# Schematic.net
KiCad netlist of a schematic drawn in Altium Designer
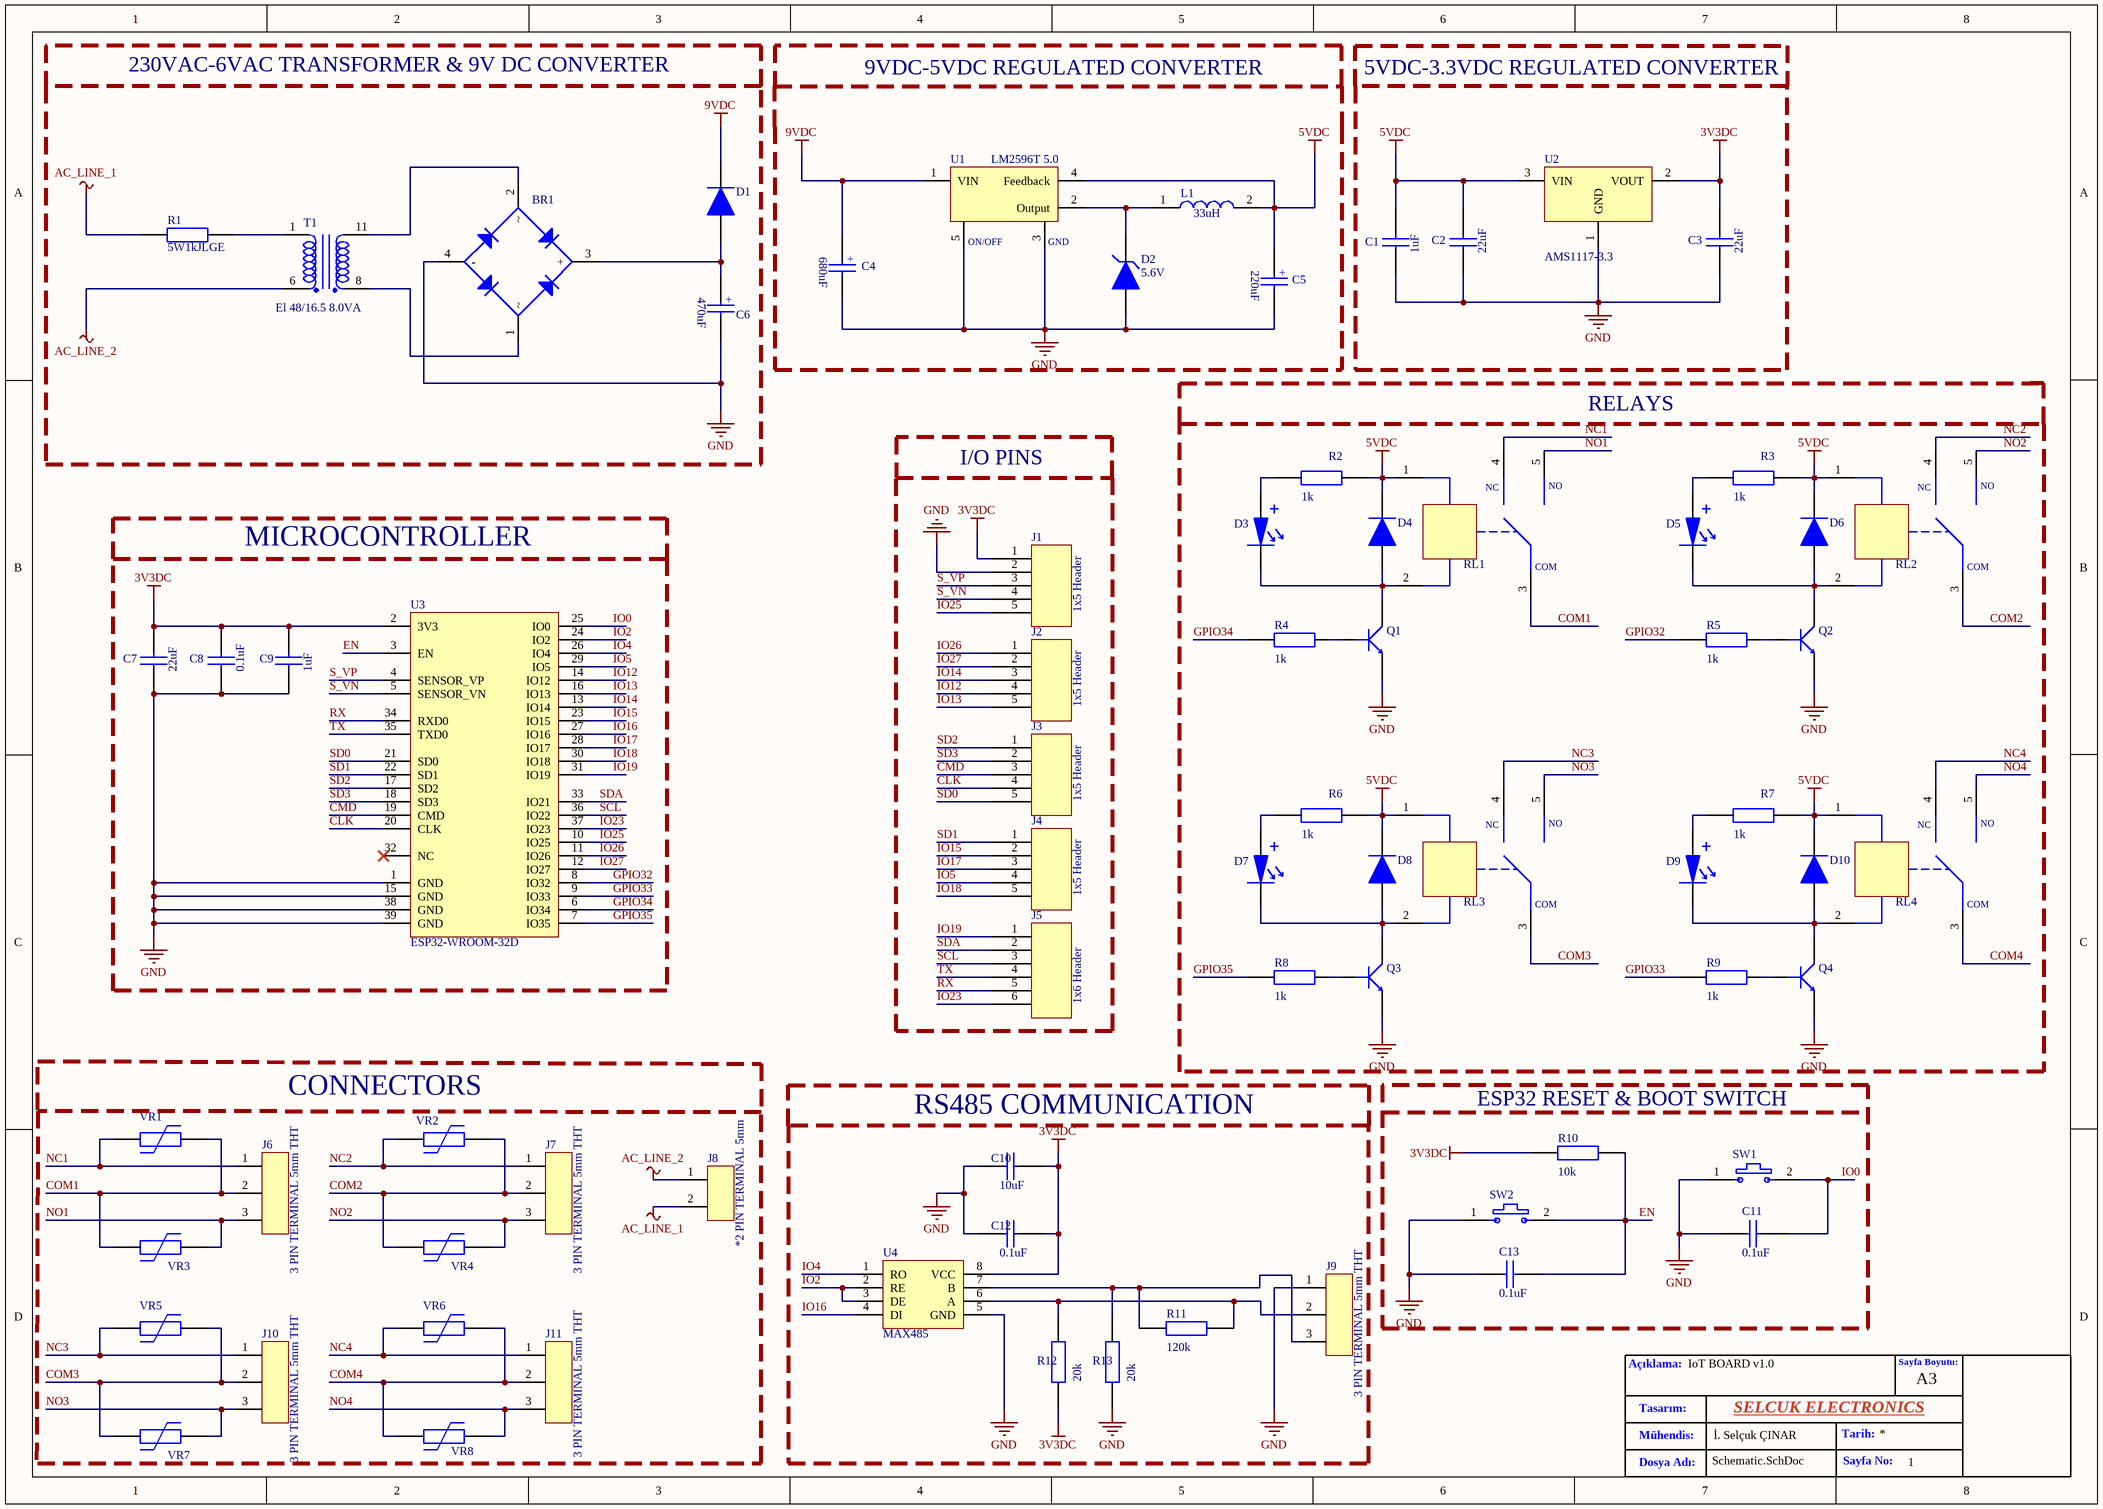
[diagram p0: Schematic.SchDoc]

(export (version "E")
  (design (tool "Eeschema 10.0.6"))
  (components
    (comp (ref "BR1")
      (value "MB10M")
      (footprint "MB10M")
      (description "Bridge Diode AC-DC")
      (libsource (lib "Sch_Lib") (part "MB10M"))
    )
    (comp (ref "C1")
      (value "CAP CER 22uF 0805")
      (footprint "CAP CER 1uF 0805")
      (description "1uF 16V 10% x5R 805 SMD Capacitor")
      (libsource (lib "Sch_Lib") (part "CAP CER 1uF 0805"))
    )
    (comp (ref "C2")
      (value "CAP CER 22uF 0805")
      (footprint "CAP CER 22uF 0805")
      (description "22uF 16V 10% x5R 805 SMD Capacitor")
      (libsource (lib "Sch_Lib") (part "CAP CER 22uF 0805"))
    )
    (comp (ref "C3")
      (value "CAP CER 22uF 0805")
      (footprint "CAP CER 22uF 0805")
      (description "22uF 16V 10% x5R 805 SMD Capacitor")
      (libsource (lib "Sch_Lib") (part "CAP CER 22uF 0805"))
    )
    (comp (ref "C4")
      (value "CAP ALU 680uF SMD RADIAL")
      (footprint "CAP ALU 680uF SMD RADIAL")
      (description "CAP ALU 680uF SMD")
      (libsource (lib "Sch_Lib") (part "CAP ALU 680uF SMD RADIAL"))
    )
    (comp (ref "C5")
      (value "CAP ALU 220uF SMD RADIAL")
      (footprint "CAP ALU 220uF SMD RADIAL")
      (description "CAP ALU 220uF SMD")
      (libsource (lib "Sch_Lib") (part "CAP ALU 220uF SMD RADIAL"))
    )
    (comp (ref "C6")
      (value "NOBBY")
      (footprint "CAP ALU 470uF THT")
      (description "CAP ALU 470uF Normal")
      (libsource (lib "Sch_Lib") (part "CAP ALU 470uF THT"))
    )
    (comp (ref "C7")
      (value "CAP CER 22uF 0805")
      (footprint "CAP CER 22uF 0805")
      (description "22uF 16V 10% x5R 805 SMD Capacitor")
      (libsource (lib "Sch_Lib") (part "CAP CER 22uF 0805"))
    )
    (comp (ref "C8")
      (value "CAP CER 0.1uF 0805")
      (footprint "CAP CER 0.1uF 0805")
      (description "0.1uF 16V 10% x5R 805 SMD Capacitor")
      (libsource (lib "Sch_Lib") (part "CAP CER 0.1uF 0805"))
    )
    (comp (ref "C9")
      (value "CAP CER 22uF 0805")
      (footprint "CAP CER 1uF 0805")
      (description "1uF 16V 10% x5R 805 SMD Capacitor")
      (libsource (lib "Sch_Lib") (part "CAP CER 1uF 0805"))
    )
    (comp (ref "C10")
      (value "CAP CER 22uF 0805")
      (footprint "CAP CER 10uF 0805")
      (description "10uF 16V 10% x5R 805 SMD Capacitor")
      (libsource (lib "Sch_Lib") (part "CAP CER 10uF 0805"))
    )
    (comp (ref "C11")
      (value "CAP CER 0.1uF 0805")
      (footprint "CAP CER 0.1uF 0805")
      (description "0.1uF 16V 10% x5R 805 SMD Capacitor")
      (libsource (lib "Sch_Lib") (part "CAP CER 0.1uF 0805"))
    )
    (comp (ref "C12")
      (value "CAP CER 0.1uF 0805")
      (footprint "CAP CER 0.1uF 0805")
      (description "0.1uF 16V 10% x5R 805 SMD Capacitor")
      (libsource (lib "Sch_Lib") (part "CAP CER 0.1uF 0805"))
    )
    (comp (ref "C13")
      (value "CAP CER 0.1uF 0805")
      (footprint "CAP CER 0.1uF 0805")
      (description "0.1uF 16V 10% x5R 805 SMD Capacitor")
      (libsource (lib "Sch_Lib") (part "CAP CER 0.1uF 0805"))
    )
    (comp (ref "D1")
      (value "M7-KT 1N4007 SMD")
      (footprint "M7-KT 1N4007 SMD")
      (description "M7-KT - 1N4007 - SMD Diyot 1A 1000V")
      (libsource (lib "Sch_Lib") (part "M7-KT 1N4007 SMD"))
    )
    (comp (ref "D2")
      (value "1SMB5919BT3G")
      (footprint "SMB")
      (description "Diode Zener Single 5.6V 5% 3W 2-Pin SMB T/R")
      (fields
        (field (name "MANUFACTURER") "ON Semiconductor")
        (field (name "TOLERANCE") "5%")
        (field (name "WORKING VOLTAGE") "5.6V")
        (field (name "DESIGNED BY") "BERK")
      )
      (libsource (lib "UDEMY_Library") (part "1SMB5919BT3G"))
    )
    (comp (ref "D3")
      (value "LED RED THT")
      (footprint "LED RED THT")
      (description "Throught LED")
      (libsource (lib "Sch_Lib") (part "LED RED THT"))
    )
    (comp (ref "D4")
      (value "M7-KT 1N4007 SMD")
      (footprint "M7-KT 1N4007 SMD")
      (description "M7-KT - 1N4007 - SMD Diyot 1A 1000V")
      (libsource (lib "Sch_Lib") (part "M7-KT 1N4007 SMD"))
    )
    (comp (ref "D5")
      (value "LED RED THT")
      (footprint "LED RED THT")
      (description "Throught LED")
      (libsource (lib "Sch_Lib") (part "LED RED THT"))
    )
    (comp (ref "D6")
      (value "M7-KT 1N4007 SMD")
      (footprint "M7-KT 1N4007 SMD")
      (description "M7-KT - 1N4007 - SMD Diyot 1A 1000V")
      (libsource (lib "Sch_Lib") (part "M7-KT 1N4007 SMD"))
    )
    (comp (ref "D7")
      (value "LED RED THT")
      (footprint "LED RED THT")
      (description "Throught LED")
      (libsource (lib "Sch_Lib") (part "LED RED THT"))
    )
    (comp (ref "D8")
      (value "M7-KT 1N4007 SMD")
      (footprint "M7-KT 1N4007 SMD")
      (description "M7-KT - 1N4007 - SMD Diyot 1A 1000V")
      (libsource (lib "Sch_Lib") (part "M7-KT 1N4007 SMD"))
    )
    (comp (ref "D9")
      (value "LED RED THT")
      (footprint "LED RED THT")
      (description "Throught LED")
      (libsource (lib "Sch_Lib") (part "LED RED THT"))
    )
    (comp (ref "D10")
      (value "M7-KT 1N4007 SMD")
      (footprint "M7-KT 1N4007 SMD")
      (description "M7-KT - 1N4007 - SMD Diyot 1A 1000V")
      (libsource (lib "Sch_Lib") (part "M7-KT 1N4007 SMD"))
    )
    (comp (ref "J1")
      (value "1x5 Header")
      (footprint "1x5 Header")
      (libsource (lib "Sch_Lib") (part "1x5 Header"))
    )
    (comp (ref "J2")
      (value "1x5 Header")
      (footprint "1x5 Header")
      (libsource (lib "Sch_Lib") (part "1x5 Header"))
    )
    (comp (ref "J3")
      (value "1x5 Header")
      (footprint "1x5 Header")
      (libsource (lib "Sch_Lib") (part "1x5 Header"))
    )
    (comp (ref "J4")
      (value "1x5 Header")
      (footprint "1x5 Header")
      (libsource (lib "Sch_Lib") (part "1x5 Header"))
    )
    (comp (ref "J5")
      (value "1x6 Header")
      (footprint "1x6 Header")
      (libsource (lib "Sch_Lib") (part "1x6 Header"))
    )
    (comp (ref "J6")
      (value "3 PIN TERMINAL 5mm THT")
      (footprint "3 PIN TERMINAL 5mm THT")
      (description "3 Position Wire to Board Terminal Block Horizontal with Board 0.197\" (5.00mm) Through Hole")
      (libsource (lib "Sch_Lib") (part "3 PIN TERMINAL 5mm THT"))
    )
    (comp (ref "J7")
      (value "3 PIN TERMINAL 5mm THT")
      (footprint "3 PIN TERMINAL 5mm THT")
      (description "3 Position Wire to Board Terminal Block Horizontal with Board 0.197\" (5.00mm) Through Hole")
      (libsource (lib "Sch_Lib") (part "3 PIN TERMINAL 5mm THT"))
    )
    (comp (ref "J8")
      (value "*2 PIN TERMINAL 5mm")
      (footprint "2 PIN TERMINAL 5mm THT")
      (description "2 Position Wire to Board Terminal Block Horizontal with Board 0.197\" (5.00mm) Through Hole")
      (libsource (lib "Sch_Lib") (part "2 PIN TERMINAL 5mm THT"))
    )
    (comp (ref "J9")
      (value "3 PIN TERMINAL 5mm THT")
      (footprint "3 PIN TERMINAL 5mm THT")
      (description "3 Position Wire to Board Terminal Block Horizontal with Board 0.197\" (5.00mm) Through Hole")
      (libsource (lib "Sch_Lib") (part "3 PIN TERMINAL 5mm THT"))
    )
    (comp (ref "J10")
      (value "3 PIN TERMINAL 5mm THT")
      (footprint "3 PIN TERMINAL 5mm THT")
      (description "3 Position Wire to Board Terminal Block Horizontal with Board 0.197\" (5.00mm) Through Hole")
      (libsource (lib "Sch_Lib") (part "3 PIN TERMINAL 5mm THT"))
    )
    (comp (ref "J11")
      (value "3 PIN TERMINAL 5mm THT")
      (footprint "3 PIN TERMINAL 5mm THT")
      (description "3 Position Wire to Board Terminal Block Horizontal with Board 0.197\" (5.00mm) Through Hole")
      (libsource (lib "Sch_Lib") (part "3 PIN TERMINAL 5mm THT"))
    )
    (comp (ref "L1")
      (value "SRR1260-330M")
      (footprint "SRR1260-330M")
      (description "33 µH Shielded Drum Core, Wirewound Inductor 3 A 60mOhm Max Nonstandard")
      (libsource (lib "Sch_Lib") (part "SRR1260-330M"))
    )
    (comp (ref "Q1")
      (value "BC847 NPN SMD SOT-23")
      (footprint "BC847 NPN SMD SOT-23")
      (description "BC847 Transistör NPN SMD SOT-23100mA, 45V")
      (libsource (lib "Sch_Lib") (part "BC847 NPN SMD SOT-23"))
    )
    (comp (ref "Q2")
      (value "BC847 NPN SMD SOT-23")
      (footprint "BC847 NPN SMD SOT-23")
      (description "BC847 Transistör NPN SMD SOT-23100mA, 45V")
      (libsource (lib "Sch_Lib") (part "BC847 NPN SMD SOT-23"))
    )
    (comp (ref "Q3")
      (value "BC847 NPN SMD SOT-23")
      (footprint "BC847 NPN SMD SOT-23")
      (description "BC847 Transistör NPN SMD SOT-23100mA, 45V")
      (libsource (lib "Sch_Lib") (part "BC847 NPN SMD SOT-23"))
    )
    (comp (ref "Q4")
      (value "BC847 NPN SMD SOT-23")
      (footprint "BC847 NPN SMD SOT-23")
      (description "BC847 Transistör NPN SMD SOT-23100mA, 45V")
      (libsource (lib "Sch_Lib") (part "BC847 NPN SMD SOT-23"))
    )
    (comp (ref "R1")
      (value "5W1kJLGE")
      (footprint "5W1kJLGE")
      (description "Resistor 5 Watt Cermet Wirewound Flameproof 1KOhm 5% Axial Lead")
      (libsource (lib "Sch_Lib") (part "5W1kJLGE"))
    )
    (comp (ref "R2")
      (value "RES 1K OHM 805")
      (footprint "RES 1K OHM 805")
      (description "1K 805 1/8 SMD Direnç")
      (libsource (lib "Sch_Lib") (part "RES 1K OHM 805"))
    )
    (comp (ref "R3")
      (value "RES 1K OHM 805")
      (footprint "RES 1K OHM 805")
      (description "1K 805 1/8 SMD Direnç")
      (libsource (lib "Sch_Lib") (part "RES 1K OHM 805"))
    )
    (comp (ref "R4")
      (value "RES 1K OHM 805")
      (footprint "RES 1K OHM 805")
      (description "1K 805 1/8 SMD Direnç")
      (libsource (lib "Sch_Lib") (part "RES 1K OHM 805"))
    )
    (comp (ref "R5")
      (value "RES 1K OHM 805")
      (footprint "RES 1K OHM 805")
      (description "1K 805 1/8 SMD Direnç")
      (libsource (lib "Sch_Lib") (part "RES 1K OHM 805"))
    )
    (comp (ref "R6")
      (value "RES 1K OHM 805")
      (footprint "RES 1K OHM 805")
      (description "1K 805 1/8 SMD Direnç")
      (libsource (lib "Sch_Lib") (part "RES 1K OHM 805"))
    )
    (comp (ref "R7")
      (value "RES 1K OHM 805")
      (footprint "RES 1K OHM 805")
      (description "1K 805 1/8 SMD Direnç")
      (libsource (lib "Sch_Lib") (part "RES 1K OHM 805"))
    )
    (comp (ref "R8")
      (value "RES 1K OHM 805")
      (footprint "RES 1K OHM 805")
      (description "1K 805 1/8 SMD Direnç")
      (libsource (lib "Sch_Lib") (part "RES 1K OHM 805"))
    )
    (comp (ref "R9")
      (value "RES 1K OHM 805")
      (footprint "RES 1K OHM 805")
      (description "1K 805 1/8 SMD Direnç")
      (libsource (lib "Sch_Lib") (part "RES 1K OHM 805"))
    )
    (comp (ref "R10")
      (value "RES 10K OHM 805")
      (footprint "RES 10K OHM 805")
      (description "10K 805 1/8 SMD Direnç")
      (libsource (lib "Sch_Lib") (part "RES 10K OHM 805"))
    )
    (comp (ref "R11")
      (value "RES 120R OHM 805")
      (footprint "RES 120R OHM 805")
      (description "120Ohm 805 1/8 SMD Direnç")
      (libsource (lib "Sch_Lib") (part "RES 120R OHM 805"))
    )
    (comp (ref "R12")
      (value "RES 20K OHM 805")
      (footprint "RES 20K OHM 805")
      (description "20K 805 1/8 SMD Direnç")
      (libsource (lib "Sch_Lib") (part "RES 20K OHM 805"))
    )
    (comp (ref "R13")
      (value "RES 20K OHM 805")
      (footprint "RES 20K OHM 805")
      (description "20K 805 1/8 SMD Direnç")
      (libsource (lib "Sch_Lib") (part "RES 20K OHM 805"))
    )
    (comp (ref "RL1")
      (value "SRD-03VDC-SL-C")
      (footprint "SRD-03VDC-SL-C")
      (description "Relays General Purpose Non Latching 3VDC SPDT 10A (250VAC) Max 5PIN")
      (libsource (lib "Sch_Lib") (part "SRD-03VDC-SL-C"))
    )
    (comp (ref "RL2")
      (value "SRD-03VDC-SL-C")
      (footprint "SRD-03VDC-SL-C")
      (description "Relays General Purpose Non Latching 3VDC SPDT 10A (250VAC) Max 5PIN")
      (libsource (lib "Sch_Lib") (part "SRD-03VDC-SL-C"))
    )
    (comp (ref "RL3")
      (value "SRD-03VDC-SL-C")
      (footprint "SRD-03VDC-SL-C")
      (description "Relays General Purpose Non Latching 3VDC SPDT 10A (250VAC) Max 5PIN")
      (libsource (lib "Sch_Lib") (part "SRD-03VDC-SL-C"))
    )
    (comp (ref "RL4")
      (value "SRD-03VDC-SL-C")
      (footprint "SRD-03VDC-SL-C")
      (description "Relays General Purpose Non Latching 3VDC SPDT 10A (250VAC) Max 5PIN")
      (libsource (lib "Sch_Lib") (part "SRD-03VDC-SL-C"))
    )
    (comp (ref "SW1")
      (value "SKRKAEE010")
      (footprint "SKRKAEE010")
      (description "Switch Tactile N.O. SPST Round Button Gull Wing 0.05A 12VDC 1.57N SMD T/R")
      (libsource (lib "Sch_Lib") (part "SKRKAEE010"))
    )
    (comp (ref "SW2")
      (value "SKRKAEE010")
      (footprint "SKRKAEE010")
      (description "Switch Tactile N.O. SPST Round Button Gull Wing 0.05A 12VDC 1.57N SMD T/R")
      (libsource (lib "Sch_Lib") (part "SKRKAEE010"))
    )
    (comp (ref "T1")
      (value "El 48/16.5 8.0VA")
      (footprint "El 48/16.5 8.0VA")
      (description "230VAC-6VAC Transformer 8VA")
      (libsource (lib "Sch_Lib") (part "El 48/16.5 8.0VA"))
    )
    (comp (ref "U1")
      (value "LM2596T 5.0")
      (footprint "LM2596T 5.0")
      (description "SIMPLE SWITCHER&reg; 4.5V to 40V, 3A Low Component Count Step-Down Regulator 5-TO-220")
      (libsource (lib "Sch_Lib") (part "LM2596T 5.0"))
    )
    (comp (ref "U2")
      (value "AMS1117-3.3")
      (footprint "AMS1117-3.3")
      (description "Sot223/Pkg 1-Amp 3.3-Volt Low Drop Out Voltage Regulatator")
      (libsource (lib "Sch_Lib") (part "AMS1117-3.3"))
    )
    (comp (ref "U3")
      (value "ESP32-WROOM-32D")
      (footprint "ESP32-WROOM-32D")
      (description "SMD MODULE, ESP32-D0WDQ6, 32MBIT")
      (libsource (lib "Sch_Lib") (part "ESP32-WROOM-32D"))
    )
    (comp (ref "U4")
      (value "MAX485")
      (footprint "MAX485")
      (description "1/1 Transceiver Half RS422, RS485 8-uMAX-EP¦8-uSOP-EP")
      (libsource (lib "Sch_Lib") (part "MAX485"))
    )
    (comp (ref "VR1")
      (value "B72210S0151K101")
      (footprint "B72210S0151K101")
      (description "240 V 2.5 kA Varistor 1 Circuit Through Hole Disc 10mm")
      (libsource (lib "Sch_Lib") (part "B72210S0151K101"))
    )
    (comp (ref "VR2")
      (value "B72210S0151K101")
      (footprint "B72210S0151K101")
      (description "240 V 2.5 kA Varistor 1 Circuit Through Hole Disc 10mm")
      (libsource (lib "Sch_Lib") (part "B72210S0151K101"))
    )
    (comp (ref "VR3")
      (value "B72210S0151K101")
      (footprint "B72210S0151K101")
      (description "240 V 2.5 kA Varistor 1 Circuit Through Hole Disc 10mm")
      (libsource (lib "Sch_Lib") (part "B72210S0151K101"))
    )
    (comp (ref "VR4")
      (value "B72210S0151K101")
      (footprint "B72210S0151K101")
      (description "240 V 2.5 kA Varistor 1 Circuit Through Hole Disc 10mm")
      (libsource (lib "Sch_Lib") (part "B72210S0151K101"))
    )
    (comp (ref "VR5")
      (value "B72210S0151K101")
      (footprint "B72210S0151K101")
      (description "240 V 2.5 kA Varistor 1 Circuit Through Hole Disc 10mm")
      (libsource (lib "Sch_Lib") (part "B72210S0151K101"))
    )
    (comp (ref "VR6")
      (value "B72210S0151K101")
      (footprint "B72210S0151K101")
      (description "240 V 2.5 kA Varistor 1 Circuit Through Hole Disc 10mm")
      (libsource (lib "Sch_Lib") (part "B72210S0151K101"))
    )
    (comp (ref "VR7")
      (value "B72210S0151K101")
      (footprint "B72210S0151K101")
      (description "240 V 2.5 kA Varistor 1 Circuit Through Hole Disc 10mm")
      (libsource (lib "Sch_Lib") (part "B72210S0151K101"))
    )
    (comp (ref "VR8")
      (value "B72210S0151K101")
      (footprint "B72210S0151K101")
      (description "240 V 2.5 kA Varistor 1 Circuit Through Hole Disc 10mm")
      (libsource (lib "Sch_Lib") (part "B72210S0151K101"))
    )
  )
  (nets
    (net (code "1") (name "/CLK") (class "Default")
      (node (ref "J3") (pin "4") (pinfunction "4_4") (pintype "passive"))
      (node (ref "U3") (pin "20") (pinfunction "CLK_20") (pintype "passive"))
    )
    (net (code "2") (name "/CMD") (class "Default")
      (node (ref "J3") (pin "3") (pinfunction "3_3") (pintype "passive"))
      (node (ref "U3") (pin "19") (pinfunction "CMD_19") (pintype "passive"))
    )
    (net (code "3") (name "/COM1") (class "Default")
      (node (ref "J6") (pin "2") (pinfunction "2_2") (pintype "passive"))
      (node (ref "RL1") (pin "3") (pinfunction "COM_3") (pintype "passive"))
      (node (ref "VR1") (pin "2") (pinfunction "2_2") (pintype "passive"))
      (node (ref "VR3") (pin "1") (pinfunction "1_1") (pintype "passive"))
    )
    (net (code "4") (name "/COM2") (class "Default")
      (node (ref "J7") (pin "2") (pinfunction "2_2") (pintype "passive"))
      (node (ref "RL2") (pin "3") (pinfunction "COM_3") (pintype "passive"))
      (node (ref "VR2") (pin "2") (pinfunction "2_2") (pintype "passive"))
      (node (ref "VR4") (pin "1") (pinfunction "1_1") (pintype "passive"))
    )
    (net (code "5") (name "/COM3") (class "Default")
      (node (ref "J10") (pin "2") (pinfunction "2_2") (pintype "passive"))
      (node (ref "RL3") (pin "3") (pinfunction "COM_3") (pintype "passive"))
      (node (ref "VR5") (pin "2") (pinfunction "2_2") (pintype "passive"))
      (node (ref "VR7") (pin "1") (pinfunction "1_1") (pintype "passive"))
    )
    (net (code "6") (name "/COM4") (class "Default")
      (node (ref "J11") (pin "2") (pinfunction "2_2") (pintype "passive"))
      (node (ref "RL4") (pin "3") (pinfunction "COM_3") (pintype "passive"))
      (node (ref "VR6") (pin "2") (pinfunction "2_2") (pintype "passive"))
      (node (ref "VR8") (pin "1") (pinfunction "1_1") (pintype "passive"))
    )
    (net (code "7") (name "/EN") (class "Default")
      (node (ref "C13") (pin "2") (pinfunction "2_2") (pintype "passive"))
      (node (ref "R10") (pin "2") (pinfunction "2_2") (pintype "passive"))
      (node (ref "SW2") (pin "2") (pinfunction "2_2") (pintype "passive"))
      (node (ref "U3") (pin "3") (pinfunction "EN_3") (pintype "passive"))
    )
    (net (code "8") (name "/GPIO32") (class "Default")
      (node (ref "R5") (pin "1") (pinfunction "1_1") (pintype "passive"))
      (node (ref "U3") (pin "8") (pinfunction "IO32_8") (pintype "passive"))
    )
    (net (code "9") (name "/GPIO33") (class "Default")
      (node (ref "R9") (pin "1") (pinfunction "1_1") (pintype "passive"))
      (node (ref "U3") (pin "9") (pinfunction "IO33_9") (pintype "passive"))
    )
    (net (code "10") (name "/GPIO34") (class "Default")
      (node (ref "R4") (pin "1") (pinfunction "1_1") (pintype "passive"))
      (node (ref "U3") (pin "6") (pinfunction "IO34_6") (pintype "passive"))
    )
    (net (code "11") (name "/GPIO35") (class "Default")
      (node (ref "R8") (pin "1") (pinfunction "1_1") (pintype "passive"))
      (node (ref "U3") (pin "7") (pinfunction "IO35_7") (pintype "passive"))
    )
    (net (code "12") (name "/IO0") (class "Default")
      (node (ref "C11") (pin "2") (pinfunction "2_2") (pintype "passive"))
      (node (ref "SW1") (pin "2") (pinfunction "2_2") (pintype "passive"))
      (node (ref "U3") (pin "25") (pinfunction "IO0_25") (pintype "passive"))
    )
    (net (code "13") (name "/IO2") (class "Default")
      (node (ref "U3") (pin "24") (pinfunction "IO2_24") (pintype "passive"))
      (node (ref "U4") (pin "2") (pinfunction "RE_2") (pintype "passive"))
      (node (ref "U4") (pin "3") (pinfunction "DE_3") (pintype "passive"))
    )
    (net (code "14") (name "/IO4") (class "Default")
      (node (ref "U3") (pin "26") (pinfunction "IO4_26") (pintype "passive"))
      (node (ref "U4") (pin "1") (pinfunction "RO_1") (pintype "passive"))
    )
    (net (code "15") (name "/IO5") (class "Default")
      (node (ref "J4") (pin "4") (pinfunction "4_4") (pintype "passive"))
      (node (ref "U3") (pin "29") (pinfunction "IO5_29") (pintype "passive"))
    )
    (net (code "16") (name "/IO12") (class "Default")
      (node (ref "J2") (pin "4") (pinfunction "4_4") (pintype "passive"))
      (node (ref "U3") (pin "14") (pinfunction "IO12_14") (pintype "passive"))
    )
    (net (code "17") (name "/IO13") (class "Default")
      (node (ref "J2") (pin "5") (pinfunction "5_5") (pintype "passive"))
      (node (ref "U3") (pin "16") (pinfunction "IO13_16") (pintype "passive"))
    )
    (net (code "18") (name "/IO14") (class "Default")
      (node (ref "J2") (pin "3") (pinfunction "3_3") (pintype "passive"))
      (node (ref "U3") (pin "13") (pinfunction "IO14_13") (pintype "passive"))
    )
    (net (code "19") (name "/IO15") (class "Default")
      (node (ref "J4") (pin "2") (pinfunction "2_2") (pintype "passive"))
      (node (ref "U3") (pin "23") (pinfunction "IO15_23") (pintype "passive"))
    )
    (net (code "20") (name "/IO16") (class "Default")
      (node (ref "U3") (pin "27") (pinfunction "IO16_27") (pintype "passive"))
      (node (ref "U4") (pin "4") (pinfunction "DI_4") (pintype "passive"))
    )
    (net (code "21") (name "/IO17") (class "Default")
      (node (ref "J4") (pin "3") (pinfunction "3_3") (pintype "passive"))
      (node (ref "U3") (pin "28") (pinfunction "IO17_28") (pintype "passive"))
    )
    (net (code "22") (name "/IO18") (class "Default")
      (node (ref "J4") (pin "5") (pinfunction "5_5") (pintype "passive"))
      (node (ref "U3") (pin "30") (pinfunction "IO18_30") (pintype "passive"))
    )
    (net (code "23") (name "/IO19") (class "Default")
      (node (ref "J5") (pin "1") (pinfunction "1_1") (pintype "passive"))
      (node (ref "U3") (pin "31") (pinfunction "IO19_31") (pintype "passive"))
    )
    (net (code "24") (name "/IO23") (class "Default")
      (node (ref "J5") (pin "6") (pinfunction "6_6") (pintype "passive"))
      (node (ref "U3") (pin "37") (pinfunction "IO23_37") (pintype "passive"))
    )
    (net (code "25") (name "/IO25") (class "Default")
      (node (ref "J1") (pin "5") (pinfunction "5_5") (pintype "passive"))
      (node (ref "U3") (pin "10") (pinfunction "IO25_10") (pintype "passive"))
    )
    (net (code "26") (name "/IO26") (class "Default")
      (node (ref "J2") (pin "1") (pinfunction "1_1") (pintype "passive"))
      (node (ref "U3") (pin "11") (pinfunction "IO26_11") (pintype "passive"))
    )
    (net (code "27") (name "/IO27") (class "Default")
      (node (ref "J2") (pin "2") (pinfunction "2_2") (pintype "passive"))
      (node (ref "U3") (pin "12") (pinfunction "IO27_12") (pintype "passive"))
    )
    (net (code "28") (name "/NC1") (class "Default")
      (node (ref "J6") (pin "1") (pinfunction "1_1") (pintype "passive"))
      (node (ref "RL1") (pin "4") (pinfunction "NC_4") (pintype "passive"))
      (node (ref "VR1") (pin "1") (pinfunction "1_1") (pintype "passive"))
    )
    (net (code "29") (name "/NC2") (class "Default")
      (node (ref "J7") (pin "1") (pinfunction "1_1") (pintype "passive"))
      (node (ref "RL2") (pin "4") (pinfunction "NC_4") (pintype "passive"))
      (node (ref "VR2") (pin "1") (pinfunction "1_1") (pintype "passive"))
    )
    (net (code "30") (name "/NC3") (class "Default")
      (node (ref "J10") (pin "1") (pinfunction "1_1") (pintype "passive"))
      (node (ref "RL3") (pin "4") (pinfunction "NC_4") (pintype "passive"))
      (node (ref "VR5") (pin "1") (pinfunction "1_1") (pintype "passive"))
    )
    (net (code "31") (name "/NC4") (class "Default")
      (node (ref "J11") (pin "1") (pinfunction "1_1") (pintype "passive"))
      (node (ref "RL4") (pin "4") (pinfunction "NC_4") (pintype "passive"))
      (node (ref "VR6") (pin "1") (pinfunction "1_1") (pintype "passive"))
    )
    (net (code "32") (name "/NO1") (class "Default")
      (node (ref "J6") (pin "3") (pinfunction "3_3") (pintype "passive"))
      (node (ref "RL1") (pin "5") (pinfunction "NO_5") (pintype "passive"))
      (node (ref "VR3") (pin "2") (pinfunction "2_2") (pintype "passive"))
    )
    (net (code "33") (name "/NO2") (class "Default")
      (node (ref "J7") (pin "3") (pinfunction "3_3") (pintype "passive"))
      (node (ref "RL2") (pin "5") (pinfunction "NO_5") (pintype "passive"))
      (node (ref "VR4") (pin "2") (pinfunction "2_2") (pintype "passive"))
    )
    (net (code "34") (name "/NO3") (class "Default")
      (node (ref "J10") (pin "3") (pinfunction "3_3") (pintype "passive"))
      (node (ref "RL3") (pin "5") (pinfunction "NO_5") (pintype "passive"))
      (node (ref "VR7") (pin "2") (pinfunction "2_2") (pintype "passive"))
    )
    (net (code "35") (name "/NO4") (class "Default")
      (node (ref "J11") (pin "3") (pinfunction "3_3") (pintype "passive"))
      (node (ref "RL4") (pin "5") (pinfunction "NO_5") (pintype "passive"))
      (node (ref "VR8") (pin "2") (pinfunction "2_2") (pintype "passive"))
    )
    (net (code "36") (name "/RX") (class "Default")
      (node (ref "J5") (pin "5") (pinfunction "5_5") (pintype "passive"))
      (node (ref "U3") (pin "34") (pinfunction "RXD0_34") (pintype "passive"))
    )
    (net (code "37") (name "/SCL") (class "Default")
      (node (ref "J5") (pin "3") (pinfunction "3_3") (pintype "passive"))
      (node (ref "U3") (pin "36") (pinfunction "IO22_36") (pintype "passive"))
    )
    (net (code "38") (name "/SD0") (class "Default")
      (node (ref "J3") (pin "5") (pinfunction "5_5") (pintype "passive"))
      (node (ref "U3") (pin "21") (pinfunction "SD0_21") (pintype "passive"))
    )
    (net (code "39") (name "/SD1") (class "Default")
      (node (ref "J4") (pin "1") (pinfunction "1_1") (pintype "passive"))
      (node (ref "U3") (pin "22") (pinfunction "SD1_22") (pintype "passive"))
    )
    (net (code "40") (name "/SD2") (class "Default")
      (node (ref "J3") (pin "1") (pinfunction "1_1") (pintype "passive"))
      (node (ref "U3") (pin "17") (pinfunction "SD2_17") (pintype "passive"))
    )
    (net (code "41") (name "/SD3") (class "Default")
      (node (ref "J3") (pin "2") (pinfunction "2_2") (pintype "passive"))
      (node (ref "U3") (pin "18") (pinfunction "SD3_18") (pintype "passive"))
    )
    (net (code "42") (name "/SDA") (class "Default")
      (node (ref "J5") (pin "2") (pinfunction "2_2") (pintype "passive"))
      (node (ref "U3") (pin "33") (pinfunction "IO21_33") (pintype "passive"))
    )
    (net (code "43") (name "/S_VN") (class "Default")
      (node (ref "J1") (pin "4") (pinfunction "4_4") (pintype "passive"))
      (node (ref "U3") (pin "5") (pinfunction "SENSOR_VN_5") (pintype "passive"))
    )
    (net (code "44") (name "/S_VP") (class "Default")
      (node (ref "J1") (pin "3") (pinfunction "3_3") (pintype "passive"))
      (node (ref "U3") (pin "4") (pinfunction "SENSOR_VP_4") (pintype "passive"))
    )
    (net (code "45") (name "/TX") (class "Default")
      (node (ref "J5") (pin "4") (pinfunction "4_4") (pintype "passive"))
      (node (ref "U3") (pin "35") (pinfunction "TXD0_35") (pintype "passive"))
    )
    (net (code "46") (name "3V3DC") (class "Default")
      (node (ref "C10") (pin "2") (pinfunction "2_2") (pintype "passive"))
      (node (ref "C12") (pin "2") (pinfunction "2_2") (pintype "passive"))
      (node (ref "C3") (pin "2") (pinfunction "2_2") (pintype "passive"))
      (node (ref "C7") (pin "2") (pinfunction "2_2") (pintype "passive"))
      (node (ref "C8") (pin "2") (pinfunction "2_2") (pintype "passive"))
      (node (ref "C9") (pin "2") (pinfunction "2_2") (pintype "passive"))
      (node (ref "J1") (pin "1") (pinfunction "1_1") (pintype "passive"))
      (node (ref "R10") (pin "1") (pinfunction "1_1") (pintype "passive"))
      (node (ref "R12") (pin "1") (pinfunction "1_1") (pintype "passive"))
      (node (ref "U2") (pin "2") (pinfunction "VOUT_2") (pintype "passive"))
      (node (ref "U3") (pin "2") (pinfunction "3V3_2") (pintype "passive"))
      (node (ref "U4") (pin "8") (pinfunction "VCC_8") (pintype "passive"))
    )
    (net (code "47") (name "5VDC") (class "Default")
      (node (ref "C1") (pin "2") (pinfunction "2_2") (pintype "passive"))
      (node (ref "C2") (pin "2") (pinfunction "2_2") (pintype "passive"))
      (node (ref "C5") (pin "1") (pinfunction "1_1") (pintype "passive"))
      (node (ref "D10") (pin "2") (pinfunction "2_2") (pintype "power_in"))
      (node (ref "D4") (pin "2") (pinfunction "2_2") (pintype "power_in"))
      (node (ref "D6") (pin "2") (pinfunction "2_2") (pintype "power_in"))
      (node (ref "D8") (pin "2") (pinfunction "2_2") (pintype "power_in"))
      (node (ref "L1") (pin "2") (pinfunction "2_2") (pintype "passive"))
      (node (ref "R2") (pin "2") (pinfunction "2_2") (pintype "passive"))
      (node (ref "R3") (pin "2") (pinfunction "2_2") (pintype "passive"))
      (node (ref "R6") (pin "2") (pinfunction "2_2") (pintype "passive"))
      (node (ref "R7") (pin "2") (pinfunction "2_2") (pintype "passive"))
      (node (ref "RL1") (pin "1") (pinfunction "+_1") (pintype "passive"))
      (node (ref "RL2") (pin "1") (pinfunction "+_1") (pintype "passive"))
      (node (ref "RL3") (pin "1") (pinfunction "+_1") (pintype "passive"))
      (node (ref "RL4") (pin "1") (pinfunction "+_1") (pintype "passive"))
      (node (ref "U1") (pin "4") (pinfunction "Feedback_4") (pintype "passive"))
      (node (ref "U2") (pin "3") (pinfunction "VIN_3") (pintype "passive"))
    )
    (net (code "48") (name "9VDC") (class "Default")
      (node (ref "C4") (pin "1") (pinfunction "1_1") (pintype "passive"))
      (node (ref "D1") (pin "2") (pinfunction "2_2") (pintype "power_in"))
      (node (ref "U1") (pin "1") (pinfunction "VIN_1") (pintype "passive"))
    )
    (net (code "49") (name "AC_LINE_1") (class "Default")
      (node (ref "J8") (pin "2") (pinfunction "2_2") (pintype "passive"))
      (node (ref "R1") (pin "1") (pinfunction "1_1") (pintype "passive"))
    )
    (net (code "50") (name "AC_LINE_2") (class "Default")
      (node (ref "J8") (pin "1") (pinfunction "1_1") (pintype "passive"))
      (node (ref "T1") (pin "6") (pinfunction "6_6") (pintype "passive"))
    )
    (net (code "51") (name "GND") (class "Default")
      (node (ref "BR1") (pin "4") (pinfunction "-_4") (pintype "passive"))
      (node (ref "C1") (pin "1") (pinfunction "1_1") (pintype "passive"))
      (node (ref "C10") (pin "1") (pinfunction "1_1") (pintype "passive"))
      (node (ref "C11") (pin "1") (pinfunction "1_1") (pintype "passive"))
      (node (ref "C12") (pin "1") (pinfunction "1_1") (pintype "passive"))
      (node (ref "C13") (pin "1") (pinfunction "1_1") (pintype "passive"))
      (node (ref "C2") (pin "1") (pinfunction "1_1") (pintype "passive"))
      (node (ref "C3") (pin "1") (pinfunction "1_1") (pintype "passive"))
      (node (ref "C4") (pin "2") (pinfunction "2_2") (pintype "passive"))
      (node (ref "C5") (pin "2") (pinfunction "2_2") (pintype "passive"))
      (node (ref "C6") (pin "2") (pinfunction "2_2") (pintype "passive"))
      (node (ref "C7") (pin "1") (pinfunction "1_1") (pintype "passive"))
      (node (ref "C8") (pin "1") (pinfunction "1_1") (pintype "passive"))
      (node (ref "C9") (pin "1") (pinfunction "1_1") (pintype "passive"))
      (node (ref "D2") (pin "A") (pinfunction "A_A") (pintype "passive"))
      (node (ref "J1") (pin "2") (pinfunction "2_2") (pintype "passive"))
      (node (ref "J9") (pin "1") (pinfunction "1_1") (pintype "passive"))
      (node (ref "Q1") (pin "2") (pinfunction "E_2") (pintype "power_in"))
      (node (ref "Q2") (pin "2") (pinfunction "E_2") (pintype "power_in"))
      (node (ref "Q3") (pin "2") (pinfunction "E_2") (pintype "power_in"))
      (node (ref "Q4") (pin "2") (pinfunction "E_2") (pintype "power_in"))
      (node (ref "R13") (pin "1") (pinfunction "1_1") (pintype "passive"))
      (node (ref "SW1") (pin "1") (pinfunction "1_1") (pintype "passive"))
      (node (ref "SW2") (pin "1") (pinfunction "1_1") (pintype "passive"))
      (node (ref "U1") (pin "3") (pinfunction "GND_3") (pintype "passive"))
      (node (ref "U1") (pin "5") (pinfunction "ON/OFF_5") (pintype "passive"))
      (node (ref "U2") (pin "1") (pinfunction "GND_1") (pintype "passive"))
      (node (ref "U3") (pin "1") (pinfunction "GND_1") (pintype "passive"))
      (node (ref "U3") (pin "15") (pinfunction "GND_15") (pintype "passive"))
      (node (ref "U3") (pin "38") (pinfunction "GND_38") (pintype "passive"))
      (node (ref "U3") (pin "39") (pinfunction "GND_39") (pintype "passive"))
      (node (ref "U4") (pin "5") (pinfunction "GND_5") (pintype "passive"))
    )
    (net (code "52") (name "Net-(BR1-+)") (class "Default")
      (node (ref "BR1") (pin "3") (pinfunction "+_3") (pintype "passive"))
      (node (ref "C6") (pin "1") (pinfunction "1_1") (pintype "passive"))
      (node (ref "D1") (pin "1") (pinfunction "1_1") (pintype "power_in"))
    )
    (net (code "53") (name "Net-(BR1-~-Pad1)") (class "Default")
      (node (ref "BR1") (pin "1") (pinfunction "~_1") (pintype "passive"))
      (node (ref "T1") (pin "8") (pinfunction "8_8") (pintype "passive"))
    )
    (net (code "54") (name "Net-(BR1-~-Pad2)") (class "Default")
      (node (ref "BR1") (pin "2") (pinfunction "~_2") (pintype "passive"))
      (node (ref "T1") (pin "11") (pinfunction "11_11") (pintype "passive"))
    )
    (net (code "55") (name "Net-(D3-Pad1)") (class "Default")
      (node (ref "D3") (pin "1") (pinfunction "1_1") (pintype "power_in"))
      (node (ref "R2") (pin "1") (pinfunction "1_1") (pintype "passive"))
    )
    (net (code "56") (name "Net-(D5-Pad1)") (class "Default")
      (node (ref "D5") (pin "1") (pinfunction "1_1") (pintype "power_in"))
      (node (ref "R3") (pin "1") (pinfunction "1_1") (pintype "passive"))
    )
    (net (code "57") (name "Net-(D7-Pad1)") (class "Default")
      (node (ref "D7") (pin "1") (pinfunction "1_1") (pintype "power_in"))
      (node (ref "R6") (pin "1") (pinfunction "1_1") (pintype "passive"))
    )
    (net (code "58") (name "Net-(D9-Pad1)") (class "Default")
      (node (ref "D9") (pin "1") (pinfunction "1_1") (pintype "power_in"))
      (node (ref "R7") (pin "1") (pinfunction "1_1") (pintype "passive"))
    )
    (net (code "59") (name "Net-(Q1-B)") (class "Default")
      (node (ref "Q1") (pin "1") (pinfunction "B_1") (pintype "power_in"))
      (node (ref "R4") (pin "2") (pinfunction "2_2") (pintype "passive"))
    )
    (net (code "60") (name "Net-(Q1-C)") (class "Default")
      (node (ref "D3") (pin "2") (pinfunction "2_2") (pintype "power_in"))
      (node (ref "D4") (pin "1") (pinfunction "1_1") (pintype "power_in"))
      (node (ref "Q1") (pin "3") (pinfunction "C_3") (pintype "power_in"))
      (node (ref "RL1") (pin "2") (pinfunction "-_2") (pintype "passive"))
    )
    (net (code "61") (name "Net-(Q2-B)") (class "Default")
      (node (ref "Q2") (pin "1") (pinfunction "B_1") (pintype "power_in"))
      (node (ref "R5") (pin "2") (pinfunction "2_2") (pintype "passive"))
    )
    (net (code "62") (name "Net-(Q2-C)") (class "Default")
      (node (ref "D5") (pin "2") (pinfunction "2_2") (pintype "power_in"))
      (node (ref "D6") (pin "1") (pinfunction "1_1") (pintype "power_in"))
      (node (ref "Q2") (pin "3") (pinfunction "C_3") (pintype "power_in"))
      (node (ref "RL2") (pin "2") (pinfunction "-_2") (pintype "passive"))
    )
    (net (code "63") (name "Net-(Q3-B)") (class "Default")
      (node (ref "Q3") (pin "1") (pinfunction "B_1") (pintype "power_in"))
      (node (ref "R8") (pin "2") (pinfunction "2_2") (pintype "passive"))
    )
    (net (code "64") (name "Net-(Q3-C)") (class "Default")
      (node (ref "D7") (pin "2") (pinfunction "2_2") (pintype "power_in"))
      (node (ref "D8") (pin "1") (pinfunction "1_1") (pintype "power_in"))
      (node (ref "Q3") (pin "3") (pinfunction "C_3") (pintype "power_in"))
      (node (ref "RL3") (pin "2") (pinfunction "-_2") (pintype "passive"))
    )
    (net (code "65") (name "Net-(Q4-B)") (class "Default")
      (node (ref "Q4") (pin "1") (pinfunction "B_1") (pintype "power_in"))
      (node (ref "R9") (pin "2") (pinfunction "2_2") (pintype "passive"))
    )
    (net (code "66") (name "Net-(Q4-C)") (class "Default")
      (node (ref "D10") (pin "1") (pinfunction "1_1") (pintype "power_in"))
      (node (ref "D9") (pin "2") (pinfunction "2_2") (pintype "power_in"))
      (node (ref "Q4") (pin "3") (pinfunction "C_3") (pintype "power_in"))
      (node (ref "RL4") (pin "2") (pinfunction "-_2") (pintype "passive"))
    )
    (net (code "67") (name "Net-(R1-Pad2)") (class "Default")
      (node (ref "R1") (pin "2") (pinfunction "2_2") (pintype "passive"))
      (node (ref "T1") (pin "1") (pinfunction "1_1") (pintype "passive"))
    )
    (net (code "68") (name "Net-(U1-Output)") (class "Default")
      (node (ref "D2") (pin "C") (pinfunction "C_C") (pintype "passive"))
      (node (ref "L1") (pin "1") (pinfunction "1_1") (pintype "passive"))
      (node (ref "U1") (pin "2") (pinfunction "Output_2") (pintype "passive"))
    )
    (net (code "69") (name "Net-(U4-A)") (class "Default")
      (node (ref "J9") (pin "2") (pinfunction "2_2") (pintype "passive"))
      (node (ref "R11") (pin "2") (pinfunction "2_2") (pintype "passive"))
      (node (ref "R12") (pin "2") (pinfunction "2_2") (pintype "passive"))
      (node (ref "U4") (pin "6") (pinfunction "A_6") (pintype "passive"))
    )
    (net (code "70") (name "Net-(U4-B)") (class "Default")
      (node (ref "J9") (pin "3") (pinfunction "3_3") (pintype "passive"))
      (node (ref "R11") (pin "1") (pinfunction "1_1") (pintype "passive"))
      (node (ref "R13") (pin "2") (pinfunction "2_2") (pintype "passive"))
      (node (ref "U4") (pin "7") (pinfunction "B_7") (pintype "passive"))
    )
    (net (code "71") (name "unconnected-(U3-NC-Pad32)") (class "Default")
      (node (ref "U3") (pin "32") (pinfunction "NC_32") (pintype "passive+no_connect"))
    )
  )
)
